# ATX_Power_Breakout_v1p0.net
KiCad netlist of a schematic drawn in EAGLE
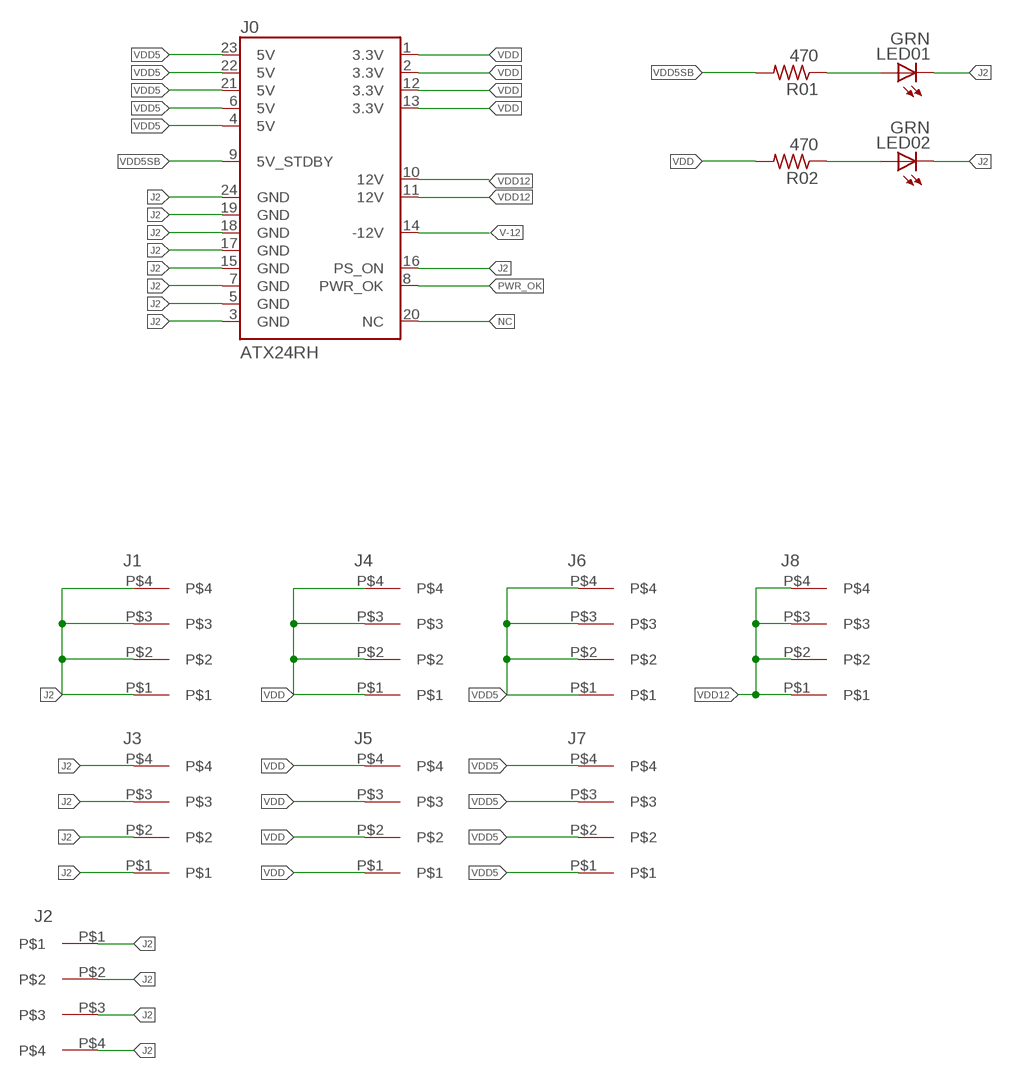
[diagram p0: schematic, sheet 1]

(export (version "E")
  (design (tool "Eeschema 10.0.6"))
  (components
    (comp (ref "J0")
      (value "ATX24RH")
      (footprint "eagle-import:ATX24_RIGHT_ANGLE")
      (libsource (lib "eagle-import") (part "ATX24RH"))
    )
    (comp (ref "J1")
      (value "3.81MM_1_X_4_RT_ANGLE_PLUG_HEADER")
      (footprint "eagle-import:1X4_3.81MM_PITCH")
      (libsource (lib "eagle-import") (part "3.81MM_1_X_4_RT_ANGLE_PLUG_HEADER"))
    )
    (comp (ref "J2")
      (value "3.81MM_1_X_4_RT_ANGLE_PLUG_HEADER")
      (footprint "eagle-import:1X4_3.81MM_PITCH")
      (libsource (lib "eagle-import") (part "3.81MM_1_X_4_RT_ANGLE_PLUG_HEADER"))
    )
    (comp (ref "J3")
      (value "3.81MM_1_X_4_RT_ANGLE_PLUG_HEADER")
      (footprint "eagle-import:1X4_3.81MM_PITCH")
      (libsource (lib "eagle-import") (part "3.81MM_1_X_4_RT_ANGLE_PLUG_HEADER"))
    )
    (comp (ref "J4")
      (value "3.81MM_1_X_4_RT_ANGLE_PLUG_HEADER")
      (footprint "eagle-import:1X4_3.81MM_PITCH")
      (libsource (lib "eagle-import") (part "3.81MM_1_X_4_RT_ANGLE_PLUG_HEADER"))
    )
    (comp (ref "J5")
      (value "3.81MM_1_X_4_RT_ANGLE_PLUG_HEADER")
      (footprint "eagle-import:1X4_3.81MM_PITCH")
      (libsource (lib "eagle-import") (part "3.81MM_1_X_4_RT_ANGLE_PLUG_HEADER"))
    )
    (comp (ref "J6")
      (value "3.81MM_1_X_4_RT_ANGLE_PLUG_HEADER")
      (footprint "eagle-import:1X4_3.81MM_PITCH")
      (libsource (lib "eagle-import") (part "3.81MM_1_X_4_RT_ANGLE_PLUG_HEADER"))
    )
    (comp (ref "J7")
      (value "3.81MM_1_X_4_RT_ANGLE_PLUG_HEADER")
      (footprint "eagle-import:1X4_3.81MM_PITCH")
      (libsource (lib "eagle-import") (part "3.81MM_1_X_4_RT_ANGLE_PLUG_HEADER"))
    )
    (comp (ref "J8")
      (value "3.81MM_1_X_4_RT_ANGLE_PLUG_HEADER")
      (footprint "eagle-import:1X4_3.81MM_PITCH")
      (libsource (lib "eagle-import") (part "3.81MM_1_X_4_RT_ANGLE_PLUG_HEADER"))
    )
    (comp (ref "LED01")
      (value "GREEN")
      (footprint "eagle-import:LED_0805_GREEN")
      (libsource (lib "eagle-import") (part "LED_0805_GREEN"))
    )
    (comp (ref "LED02")
      (value "GREEN")
      (footprint "eagle-import:LED_0805_GREEN")
      (libsource (lib "eagle-import") (part "LED_0805_GREEN"))
    )
    (comp (ref "R01")
      (value "470")
      (footprint "eagle-import:0805")
      (libsource (lib "eagle-import") (part "R_0805"))
    )
    (comp (ref "R02")
      (value "470")
      (footprint "eagle-import:0805")
      (libsource (lib "eagle-import") (part "R_0805"))
    )
  )
  (nets
    (net (code "1") (name "J2") (class "Default")
      (node (ref "J0") (pin "15") (pinfunction "GND_15") (pintype "bidirectional"))
      (node (ref "J0") (pin "16") (pinfunction "PS_ON_16") (pintype "bidirectional"))
      (node (ref "J0") (pin "17") (pinfunction "GND_17") (pintype "bidirectional"))
      (node (ref "J0") (pin "18") (pinfunction "GND_18") (pintype "bidirectional"))
      (node (ref "J0") (pin "19") (pinfunction "GND_19") (pintype "bidirectional"))
      (node (ref "J0") (pin "24") (pinfunction "GND_24") (pintype "bidirectional"))
      (node (ref "J0") (pin "3") (pinfunction "GND_3") (pintype "bidirectional"))
      (node (ref "J0") (pin "5") (pinfunction "GND_5") (pintype "bidirectional"))
      (node (ref "J0") (pin "7") (pinfunction "GND_7") (pintype "bidirectional"))
      (node (ref "J1") (pin "P$1") (pinfunction "P$1_P$1") (pintype "bidirectional"))
      (node (ref "J1") (pin "P$2") (pinfunction "P$2_P$2") (pintype "bidirectional"))
      (node (ref "J1") (pin "P$3") (pinfunction "P$3_P$3") (pintype "bidirectional"))
      (node (ref "J1") (pin "P$4") (pinfunction "P$4_P$4") (pintype "bidirectional"))
      (node (ref "J2") (pin "P$1") (pinfunction "P$1_P$1") (pintype "bidirectional"))
      (node (ref "J2") (pin "P$2") (pinfunction "P$2_P$2") (pintype "bidirectional"))
      (node (ref "J2") (pin "P$3") (pinfunction "P$3_P$3") (pintype "bidirectional"))
      (node (ref "J2") (pin "P$4") (pinfunction "P$4_P$4") (pintype "bidirectional"))
      (node (ref "J3") (pin "P$1") (pinfunction "P$1_P$1") (pintype "bidirectional"))
      (node (ref "J3") (pin "P$2") (pinfunction "P$2_P$2") (pintype "bidirectional"))
      (node (ref "J3") (pin "P$3") (pinfunction "P$3_P$3") (pintype "bidirectional"))
      (node (ref "J3") (pin "P$4") (pinfunction "P$4_P$4") (pintype "bidirectional"))
      (node (ref "LED01") (pin "C") (pinfunction "C_C") (pintype "passive"))
      (node (ref "LED02") (pin "C") (pinfunction "C_C") (pintype "passive"))
    )
    (net (code "2") (name "NC") (class "Default")
      (node (ref "J0") (pin "20") (pinfunction "NC_20") (pintype "bidirectional"))
    )
    (net (code "3") (name "Net-(LED01-PadA)") (class "Default")
      (node (ref "LED01") (pin "A") (pinfunction "A_A") (pintype "passive"))
      (node (ref "R01") (pin "1") (pinfunction "1_1") (pintype "passive"))
    )
    (net (code "4") (name "Net-(LED02-PadA)") (class "Default")
      (node (ref "LED02") (pin "A") (pinfunction "A_A") (pintype "passive"))
      (node (ref "R02") (pin "1") (pinfunction "1_1") (pintype "passive"))
    )
    (net (code "5") (name "PWR_OK") (class "Default")
      (node (ref "J0") (pin "8") (pinfunction "PWR_OK_8") (pintype "bidirectional"))
    )
    (net (code "6") (name "V-12") (class "Default")
      (node (ref "J0") (pin "14") (pinfunction "-12V_14") (pintype "bidirectional"))
    )
    (net (code "7") (name "VDD") (class "Default")
      (node (ref "J0") (pin "1") (pinfunction "3.3V_1") (pintype "bidirectional"))
      (node (ref "J0") (pin "12") (pinfunction "3.3V_12") (pintype "bidirectional"))
      (node (ref "J0") (pin "13") (pinfunction "3.3V_13") (pintype "bidirectional"))
      (node (ref "J0") (pin "2") (pinfunction "3.3V_2") (pintype "bidirectional"))
      (node (ref "J4") (pin "P$1") (pinfunction "P$1_P$1") (pintype "bidirectional"))
      (node (ref "J4") (pin "P$2") (pinfunction "P$2_P$2") (pintype "bidirectional"))
      (node (ref "J4") (pin "P$3") (pinfunction "P$3_P$3") (pintype "bidirectional"))
      (node (ref "J4") (pin "P$4") (pinfunction "P$4_P$4") (pintype "bidirectional"))
      (node (ref "J5") (pin "P$1") (pinfunction "P$1_P$1") (pintype "bidirectional"))
      (node (ref "J5") (pin "P$2") (pinfunction "P$2_P$2") (pintype "bidirectional"))
      (node (ref "J5") (pin "P$3") (pinfunction "P$3_P$3") (pintype "bidirectional"))
      (node (ref "J5") (pin "P$4") (pinfunction "P$4_P$4") (pintype "bidirectional"))
      (node (ref "R02") (pin "2") (pinfunction "2_2") (pintype "passive"))
    )
    (net (code "8") (name "VDD5") (class "Default")
      (node (ref "J0") (pin "21") (pinfunction "5V_21") (pintype "bidirectional"))
      (node (ref "J0") (pin "22") (pinfunction "5V_22") (pintype "bidirectional"))
      (node (ref "J0") (pin "23") (pinfunction "5V_23") (pintype "bidirectional"))
      (node (ref "J0") (pin "4") (pinfunction "5V_4") (pintype "bidirectional"))
      (node (ref "J0") (pin "6") (pinfunction "5V_6") (pintype "bidirectional"))
      (node (ref "J6") (pin "P$1") (pinfunction "P$1_P$1") (pintype "bidirectional"))
      (node (ref "J6") (pin "P$2") (pinfunction "P$2_P$2") (pintype "bidirectional"))
      (node (ref "J6") (pin "P$3") (pinfunction "P$3_P$3") (pintype "bidirectional"))
      (node (ref "J6") (pin "P$4") (pinfunction "P$4_P$4") (pintype "bidirectional"))
      (node (ref "J7") (pin "P$1") (pinfunction "P$1_P$1") (pintype "bidirectional"))
      (node (ref "J7") (pin "P$2") (pinfunction "P$2_P$2") (pintype "bidirectional"))
      (node (ref "J7") (pin "P$3") (pinfunction "P$3_P$3") (pintype "bidirectional"))
      (node (ref "J7") (pin "P$4") (pinfunction "P$4_P$4") (pintype "bidirectional"))
    )
    (net (code "9") (name "VDD5SB") (class "Default")
      (node (ref "J0") (pin "9") (pinfunction "5V_STDBY_9") (pintype "bidirectional"))
      (node (ref "R01") (pin "2") (pinfunction "2_2") (pintype "passive"))
    )
    (net (code "10") (name "VDD12") (class "Default")
      (node (ref "J0") (pin "10") (pinfunction "12V_10") (pintype "bidirectional"))
      (node (ref "J0") (pin "11") (pinfunction "12V_11") (pintype "bidirectional"))
      (node (ref "J8") (pin "P$1") (pinfunction "P$1_P$1") (pintype "bidirectional"))
      (node (ref "J8") (pin "P$2") (pinfunction "P$2_P$2") (pintype "bidirectional"))
      (node (ref "J8") (pin "P$3") (pinfunction "P$3_P$3") (pintype "bidirectional"))
      (node (ref "J8") (pin "P$4") (pinfunction "P$4_P$4") (pintype "bidirectional"))
    )
  )
)
